# SensorBME680.net
KiCad netlist of a schematic drawn in Altium Designer
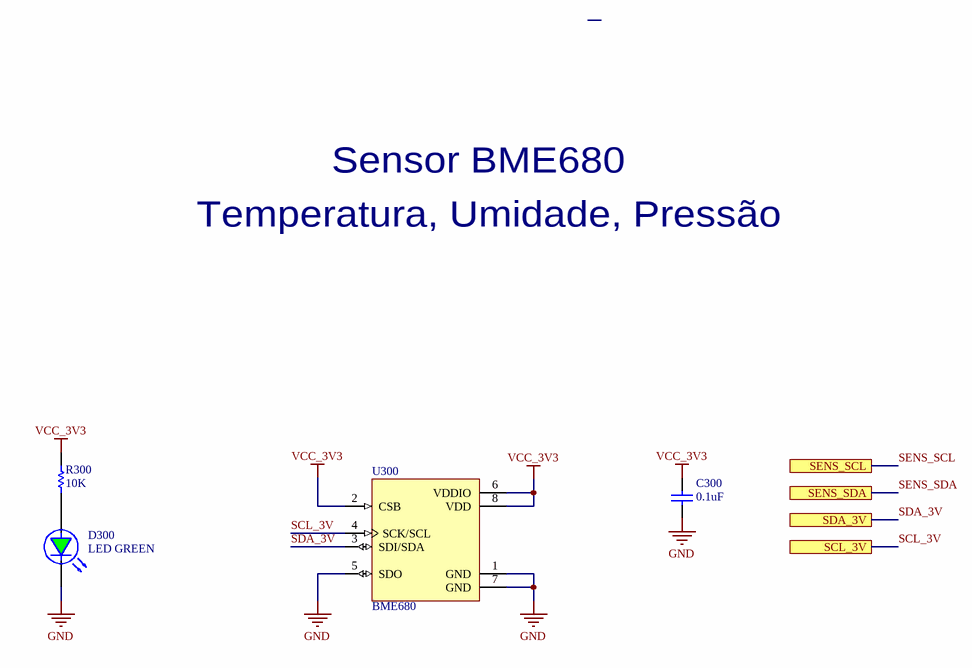
[diagram p0: SensorBME680.SchDoc]

(export (version "E")
  (design (tool "Eeschema 10.0.6"))
  (components
    (comp (ref "C300")
      (value "0.1uF")
      (footprint "CAP_CER_0603")
      (libsource (lib "PCB_TCC") (part "CAP_CER_0.1uF_0603"))
    )
    (comp (ref "D300")
      (value "LED GREEN")
      (footprint "LED_GREEN_SMD_0603")
      (libsource (lib "PCB_TCC") (part "LED_GREEN_SMD_0603"))
    )
    (comp (ref "R300") (value "10K") (footprint "RES_0603") (libsource (lib "PCB_TCC") (part "RES_10K_0603")))
    (comp (ref "U300") (value "BME680") (footprint "BME680") (libsource (lib "PCB_TCC") (part "BME680")))
  )
  (nets
    (net (code "1") (name "/SCL_3V") (class "Default")
      (node (ref "U300") (pin "4") (pinfunction "SCK/SCL_4") (pintype "input"))
    )
    (net (code "2") (name "/SDA_3V") (class "Default")
      (node (ref "U300") (pin "3") (pinfunction "SDI/SDA_3") (pintype "bidirectional"))
    )
    (net (code "5") (name "GND") (class "Default")
      (node (ref "C300") (pin "1") (pinfunction "1_1") (pintype "passive"))
      (node (ref "D300") (pin "K") (pinfunction "K_K") (pintype "passive"))
      (node (ref "U300") (pin "1") (pinfunction "GND_1") (pintype "power_in"))
      (node (ref "U300") (pin "5") (pinfunction "SDO_5") (pintype "bidirectional"))
      (node (ref "U300") (pin "7") (pinfunction "GND_7") (pintype "power_in"))
    )
    (net (code "6") (name "Net-(D300-PadA)") (class "Default")
      (node (ref "D300") (pin "A") (pinfunction "A_A") (pintype "passive"))
      (node (ref "R300") (pin "1") (pinfunction "1_1") (pintype "passive"))
    )
    (net (code "7") (name "VCC_3V3") (class "Default")
      (node (ref "C300") (pin "2") (pinfunction "2_2") (pintype "passive"))
      (node (ref "R300") (pin "2") (pinfunction "2_2") (pintype "passive"))
      (node (ref "U300") (pin "2") (pinfunction "CSB_2") (pintype "input"))
      (node (ref "U300") (pin "6") (pinfunction "VDDIO_6") (pintype "power_in"))
      (node (ref "U300") (pin "8") (pinfunction "VDD_8") (pintype "power_in"))
    )
  )
)
